# Teclas.net
KiCad netlist of a schematic drawn in EAGLE
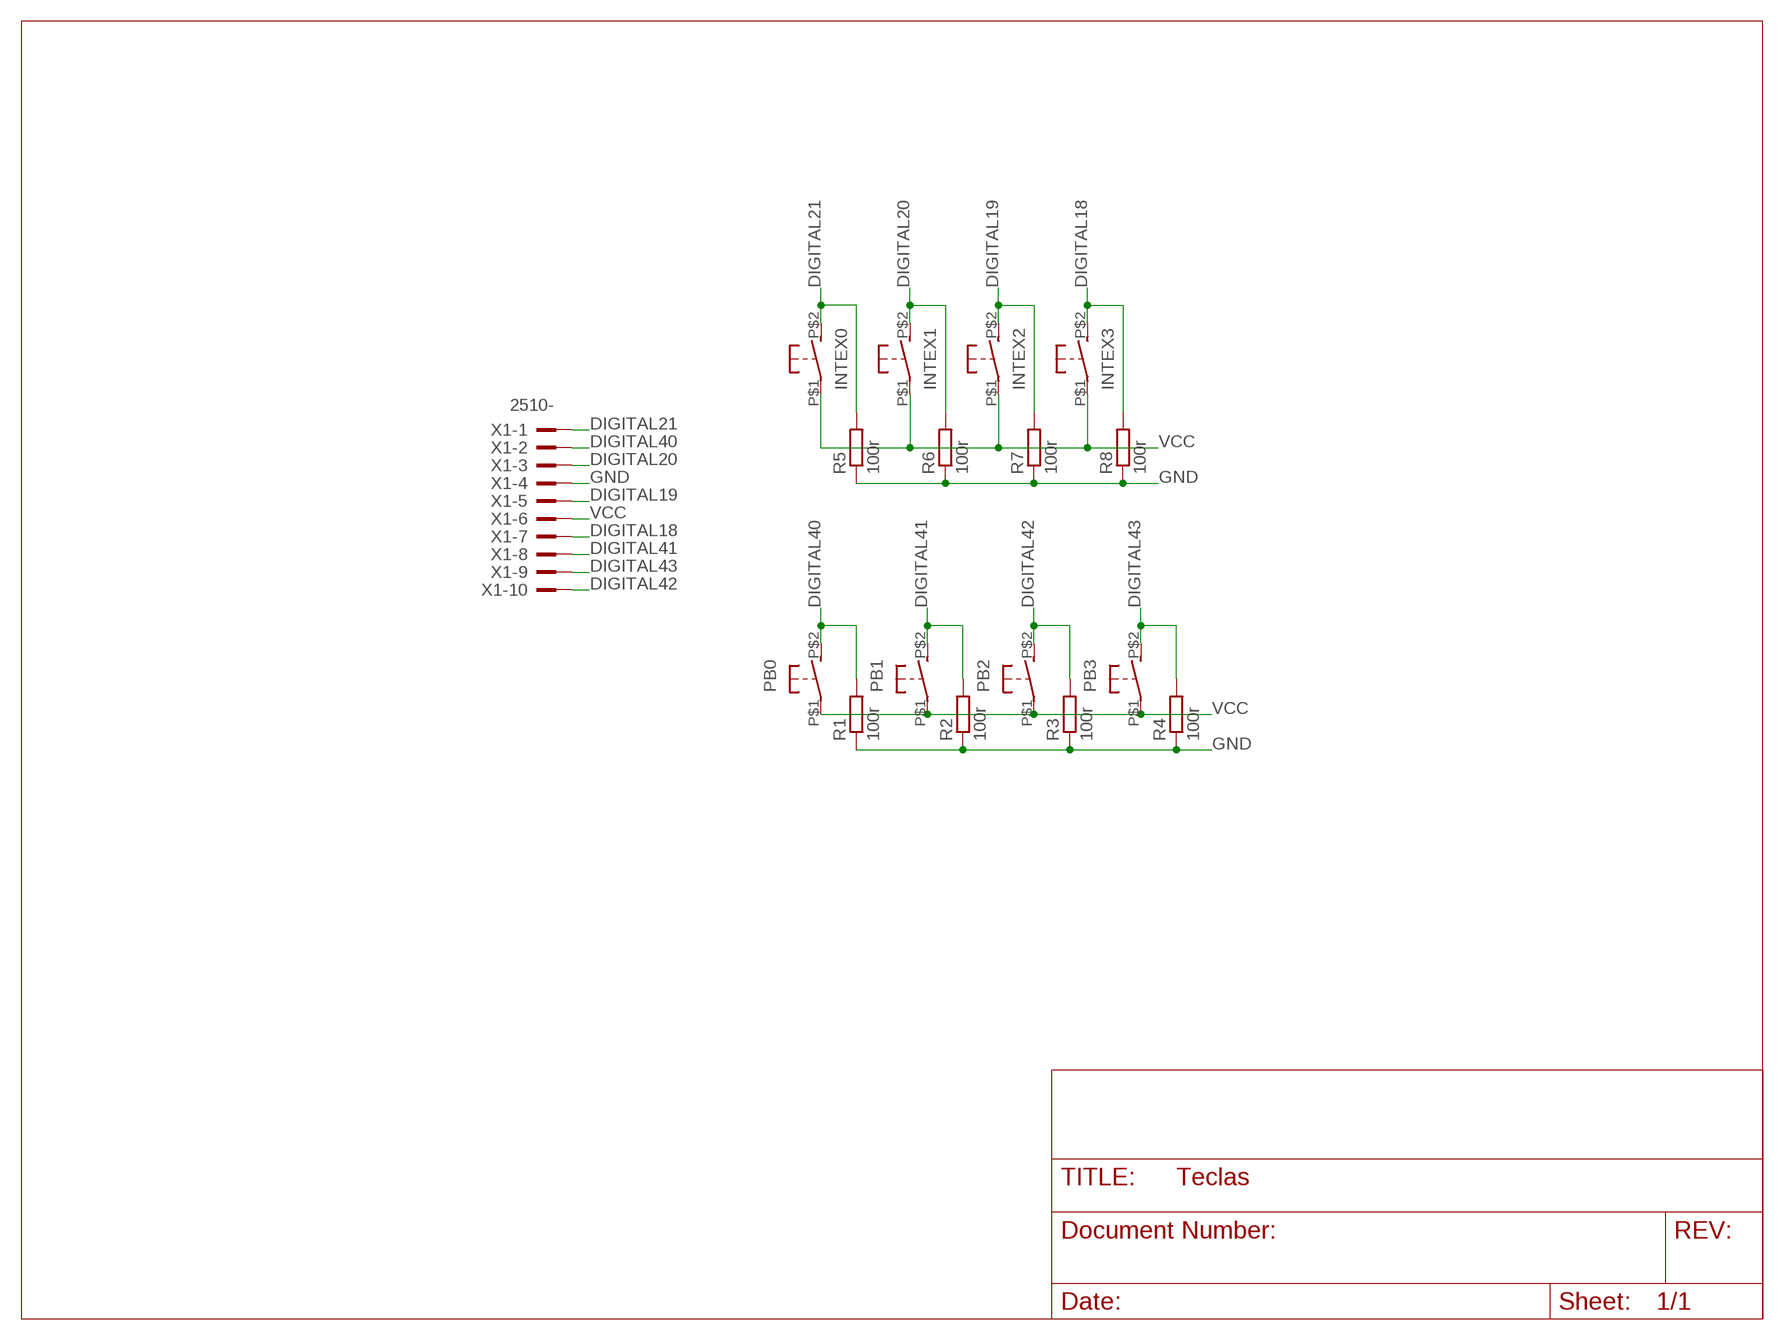
[diagram p0: schematic, sheet 1]

(export (version "E")
  (design (tool "Eeschema 10.0.6"))
  (components
    (comp (ref "INTEX0")
      (value "DS-451")
      (footprint "eagle-import:DS-451")
      (libsource (lib "eagle-import") (part "DS-451"))
    )
    (comp (ref "INTEX1")
      (value "DS-451")
      (footprint "eagle-import:DS-451")
      (libsource (lib "eagle-import") (part "DS-451"))
    )
    (comp (ref "INTEX2")
      (value "DS-451")
      (footprint "eagle-import:DS-451")
      (libsource (lib "eagle-import") (part "DS-451"))
    )
    (comp (ref "INTEX3")
      (value "DS-451")
      (footprint "eagle-import:DS-451")
      (libsource (lib "eagle-import") (part "DS-451"))
    )
    (comp (ref "PB0")
      (value "DS-451")
      (footprint "eagle-import:DS-451")
      (libsource (lib "eagle-import") (part "DS-451"))
    )
    (comp (ref "PB1")
      (value "DS-451")
      (footprint "eagle-import:DS-451")
      (libsource (lib "eagle-import") (part "DS-451"))
    )
    (comp (ref "PB2")
      (value "DS-451")
      (footprint "eagle-import:DS-451")
      (libsource (lib "eagle-import") (part "DS-451"))
    )
    (comp (ref "PB3")
      (value "DS-451")
      (footprint "eagle-import:DS-451")
      (libsource (lib "eagle-import") (part "DS-451"))
    )
    (comp (ref "R1")
      (value "100r")
      (footprint "eagle-import:0204_ELVYS")
      (libsource (lib "eagle-import") (part "R-EU_"))
    )
    (comp (ref "R2")
      (value "100r")
      (footprint "eagle-import:0204_ELVYS")
      (libsource (lib "eagle-import") (part "R-EU_"))
    )
    (comp (ref "R3")
      (value "100r")
      (footprint "eagle-import:0204_ELVYS")
      (libsource (lib "eagle-import") (part "R-EU_"))
    )
    (comp (ref "R4")
      (value "100r")
      (footprint "eagle-import:0204_ELVYS")
      (libsource (lib "eagle-import") (part "R-EU_"))
    )
    (comp (ref "R5")
      (value "100r")
      (footprint "eagle-import:0204_ELVYS")
      (libsource (lib "eagle-import") (part "R-EU_"))
    )
    (comp (ref "R6")
      (value "100r")
      (footprint "eagle-import:0204_ELVYS")
      (libsource (lib "eagle-import") (part "R-EU_"))
    )
    (comp (ref "R7")
      (value "100r")
      (footprint "eagle-import:0204_ELVYS")
      (libsource (lib "eagle-import") (part "R-EU_"))
    )
    (comp (ref "R8")
      (value "100r")
      (footprint "eagle-import:0204_ELVYS")
      (libsource (lib "eagle-import") (part "R-EU_"))
    )
    (comp (ref "X1")
      (value "2510-")
      (footprint "eagle-import:PAK100_2500-10")
      (fields (field (name "MF") "3M") (field (name "MPN") "2510-6002UB"))
      (libsource (lib "eagle-import") (part "2510-"))
    )
  )
  (nets
    (net (code "1") (name "/DIGITAL18") (class "Default")
      (node (ref "INTEX3") (pin "P$2") (pinfunction "S_P$2") (pintype "passive"))
      (node (ref "R8") (pin "P$2") (pinfunction "2_P$2") (pintype "passive"))
      (node (ref "X1") (pin "7") (pinfunction "KL_7") (pintype "passive"))
    )
    (net (code "2") (name "/DIGITAL19") (class "Default")
      (node (ref "INTEX2") (pin "P$2") (pinfunction "S_P$2") (pintype "passive"))
      (node (ref "R7") (pin "P$2") (pinfunction "2_P$2") (pintype "passive"))
      (node (ref "X1") (pin "5") (pinfunction "KL_5") (pintype "passive"))
    )
    (net (code "3") (name "/DIGITAL20") (class "Default")
      (node (ref "INTEX1") (pin "P$2") (pinfunction "S_P$2") (pintype "passive"))
      (node (ref "R6") (pin "P$2") (pinfunction "2_P$2") (pintype "passive"))
      (node (ref "X1") (pin "3") (pinfunction "KL_3") (pintype "passive"))
    )
    (net (code "4") (name "/DIGITAL21") (class "Default")
      (node (ref "INTEX0") (pin "P$2") (pinfunction "S_P$2") (pintype "passive"))
      (node (ref "R5") (pin "P$2") (pinfunction "2_P$2") (pintype "passive"))
      (node (ref "X1") (pin "1") (pinfunction "KL_1") (pintype "passive"))
    )
    (net (code "5") (name "/DIGITAL40") (class "Default")
      (node (ref "PB0") (pin "P$2") (pinfunction "S_P$2") (pintype "passive"))
      (node (ref "R1") (pin "P$2") (pinfunction "2_P$2") (pintype "passive"))
      (node (ref "X1") (pin "2") (pinfunction "KL_2") (pintype "passive"))
    )
    (net (code "6") (name "/DIGITAL41") (class "Default")
      (node (ref "PB1") (pin "P$2") (pinfunction "S_P$2") (pintype "passive"))
      (node (ref "R2") (pin "P$2") (pinfunction "2_P$2") (pintype "passive"))
      (node (ref "X1") (pin "8") (pinfunction "KL_8") (pintype "passive"))
    )
    (net (code "7") (name "/DIGITAL42") (class "Default")
      (node (ref "PB2") (pin "P$2") (pinfunction "S_P$2") (pintype "passive"))
      (node (ref "R3") (pin "P$2") (pinfunction "2_P$2") (pintype "passive"))
      (node (ref "X1") (pin "10") (pinfunction "KL_10") (pintype "passive"))
    )
    (net (code "8") (name "/DIGITAL43") (class "Default")
      (node (ref "PB3") (pin "P$2") (pinfunction "S_P$2") (pintype "passive"))
      (node (ref "R4") (pin "P$2") (pinfunction "2_P$2") (pintype "passive"))
      (node (ref "X1") (pin "9") (pinfunction "KL_9") (pintype "passive"))
    )
    (net (code "9") (name "/GND") (class "Default")
      (node (ref "R1") (pin "P$1") (pinfunction "1_P$1") (pintype "passive"))
      (node (ref "R2") (pin "P$1") (pinfunction "1_P$1") (pintype "passive"))
      (node (ref "R3") (pin "P$1") (pinfunction "1_P$1") (pintype "passive"))
      (node (ref "R4") (pin "P$1") (pinfunction "1_P$1") (pintype "passive"))
      (node (ref "R5") (pin "P$1") (pinfunction "1_P$1") (pintype "passive"))
      (node (ref "R6") (pin "P$1") (pinfunction "1_P$1") (pintype "passive"))
      (node (ref "R7") (pin "P$1") (pinfunction "1_P$1") (pintype "passive"))
      (node (ref "R8") (pin "P$1") (pinfunction "1_P$1") (pintype "passive"))
      (node (ref "X1") (pin "4") (pinfunction "KL_4") (pintype "passive"))
    )
    (net (code "10") (name "/VCC") (class "Default")
      (node (ref "INTEX0") (pin "P$1") (pinfunction "P_P$1") (pintype "passive"))
      (node (ref "INTEX1") (pin "P$1") (pinfunction "P_P$1") (pintype "passive"))
      (node (ref "INTEX2") (pin "P$1") (pinfunction "P_P$1") (pintype "passive"))
      (node (ref "INTEX3") (pin "P$1") (pinfunction "P_P$1") (pintype "passive"))
      (node (ref "PB0") (pin "P$1") (pinfunction "P_P$1") (pintype "passive"))
      (node (ref "PB1") (pin "P$1") (pinfunction "P_P$1") (pintype "passive"))
      (node (ref "PB2") (pin "P$1") (pinfunction "P_P$1") (pintype "passive"))
      (node (ref "PB3") (pin "P$1") (pinfunction "P_P$1") (pintype "passive"))
      (node (ref "X1") (pin "6") (pinfunction "KL_6") (pintype "passive"))
    )
  )
)
